# Power_Amplifier.net
KiCad netlist of a schematic drawn in Altium Designer
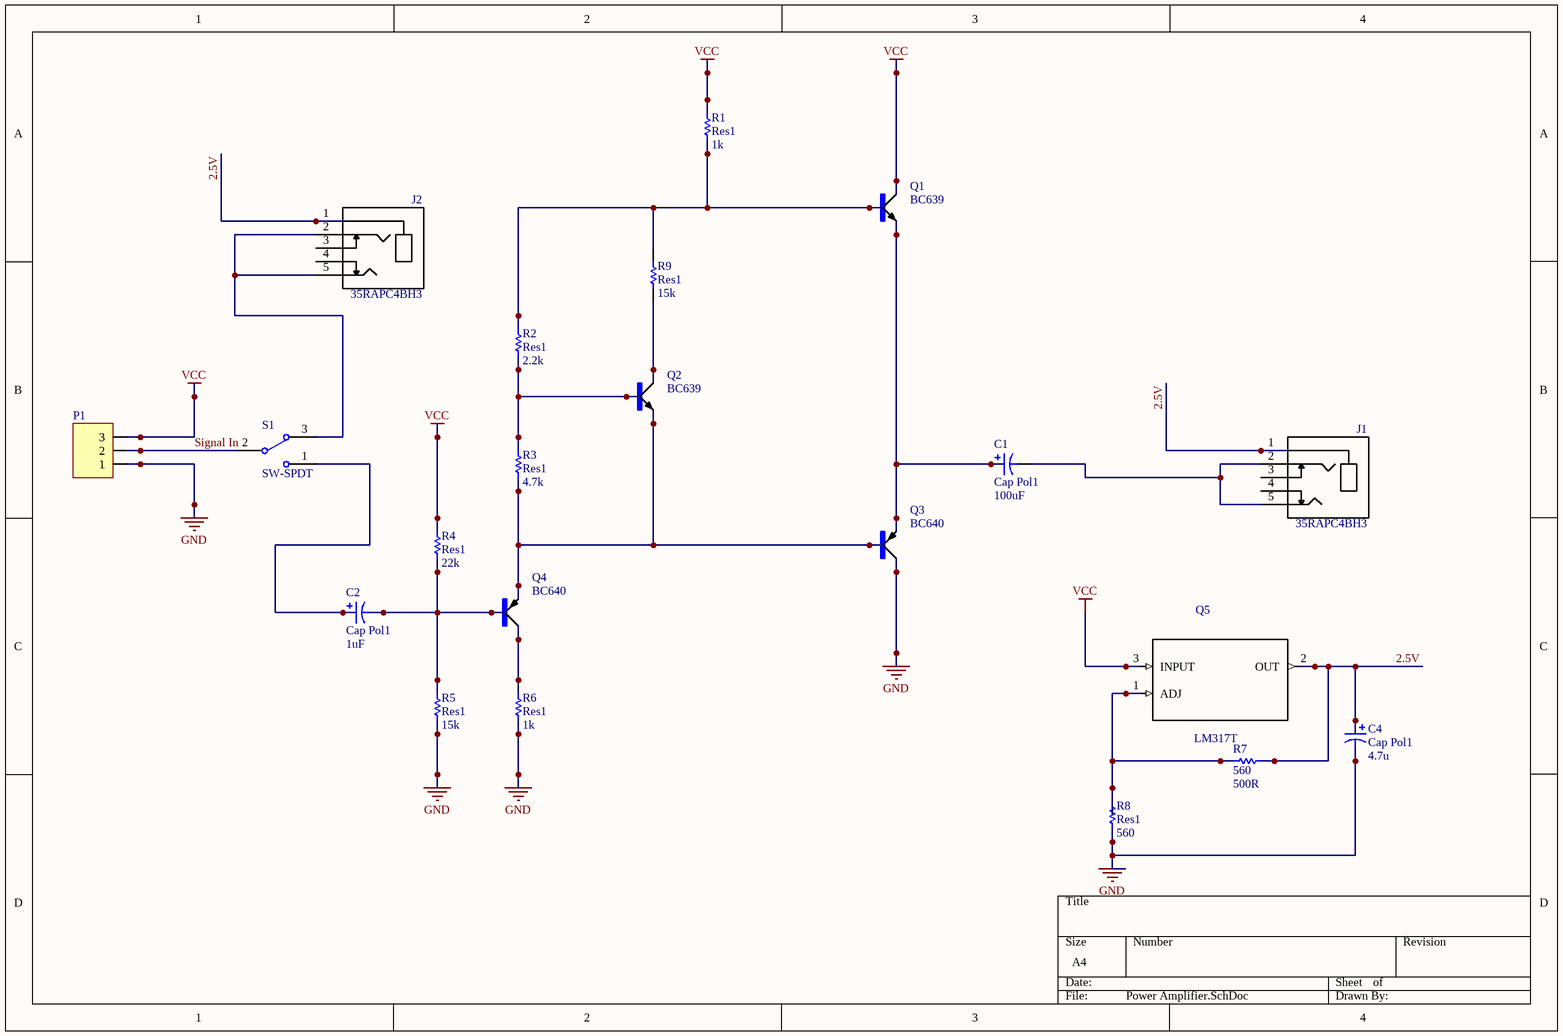
[diagram p0: Power Amplifier.SchDoc]

(export (version "E")
  (design (tool "Eeschema 10.0.6"))
  (components
    (comp (ref "C1")
      (value "Cap Pol1")
      (footprint "Capacitor 5mmx11mm")
      (description "Polarized Capacitor (Radial)")
      (fields (field (name "ALTIUM_VALUE") "100uF") (field (name "PUBLISHER") "Altium Limited"))
      (libsource (lib "Miscellaneous Devices") (part "Cap Pol1"))
    )
    (comp (ref "C2")
      (value "Cap Pol1")
      (footprint "Capacitor 5mmx11mm")
      (description "Polarized Capacitor (Radial)")
      (fields (field (name "ALTIUM_VALUE") "1uF") (field (name "PUBLISHER") "Altium Limited"))
      (libsource (lib "Miscellaneous Devices") (part "Cap Pol1"))
    )
    (comp (ref "C4")
      (value "Cap Pol1")
      (footprint "Capacitor 5mmx11mm")
      (description "Polarized Capacitor (Radial)")
      (fields (field (name "ALTIUM_VALUE") "4.7u") (field (name "PUBLISHER") "Altium Limited"))
      (libsource (lib "Miscellaneous Devices") (part "Cap Pol1"))
    )
    (comp (ref "J1")
      (value "35RAPC4BH3")
      (footprint "*SWITCHCRAFT_35RAPC4BH3")
      (description "3.50mm _0.141, 1/8, Mini Plug_ - Headphone Phone Jack Stereo _3 Conductor, TRS_ Connector Solder")
      (fields (field (name "MF") "Switchcraft Inc."))
      (libsource (lib "35RAPC4BH3") (part "35RAPC4BH3"))
    )
    (comp (ref "J2")
      (value "35RAPC4BH3")
      (footprint "*SWITCHCRAFT_35RAPC4BH3")
      (description "3.50mm _0.141, 1/8, Mini Plug_ - Headphone Phone Jack Stereo _3 Conductor, TRS_ Connector Solder")
      (fields (field (name "MF") "Switchcraft Inc."))
      (libsource (lib "35RAPC4BH3") (part "35RAPC4BH3"))
    )
    (comp (ref "P1")
      (value "~")
      (footprint "HDR1X3")
      (description "Header, 3-Pin")
      (fields (field (name "PUBLISHER") "Altium Limited"))
      (libsource (lib "Miscellaneous Connectors") (part "Header 3"))
    )
    (comp (ref "Q1")
      (value "BC639")
      (footprint "*SOT54D_BC639(Primary)")
      (description "Bipolar _BJT_ Transistor NPN 80V 1A 200MHz 625mW Through Hole TO-92-3")
      (fields (field (name "MF") "ON Semiconductor"))
      (libsource (lib "BC639") (part "BC639"))
    )
    (comp (ref "Q2")
      (value "BC639")
      (footprint "*SOT54D_BC639(Primary)")
      (description "Bipolar _BJT_ Transistor NPN 80V 1A 200MHz 625mW Through Hole TO-92-3")
      (fields (field (name "MF") "ON Semiconductor"))
      (libsource (lib "BC639") (part "BC639"))
    )
    (comp (ref "Q3")
      (value "BC640")
      (footprint "*TO92127P520H534-3")
      (description "Bipolar _BJT_ Transistor PNP 80V 500mA 150MHz 625mW Through Hole TO-92-3")
      (fields (field (name "MF") "ON Semiconductor"))
      (libsource (lib "BC640") (part "BC640"))
    )
    (comp (ref "Q4")
      (value "BC640")
      (footprint "*SOT54D_BC640(Primary)")
      (description "Bipolar _BJT_ Transistor PNP 80V 500mA 150MHz 625mW Through Hole TO-92-3")
      (fields (field (name "MF") "ON Semiconductor"))
      (libsource (lib "BC640") (part "BC640"))
    )
    (comp (ref "Q5")
      (value "LM317T")
      (footprint "TO254P450X1020X2000-3P")
      (fields (field (name "MF") "Texas Instruments") (field (name "DIGI-KEY_PART_NUMBER") "LM317T-ND"))
      (libsource (lib "LM317T") (part "LM317T"))
    )
    (comp (ref "R1")
      (value "Res1")
      (footprint "AXIAL-0.3")
      (description "Resistor")
      (fields (field (name "ALTIUM_VALUE") "1k") (field (name "PUBLISHER") "Altium Limited"))
      (libsource (lib "Miscellaneous Devices") (part "Res1"))
    )
    (comp (ref "R2")
      (value "Res1")
      (footprint "AXIAL-0.3")
      (description "Resistor")
      (fields (field (name "ALTIUM_VALUE") "2.2k") (field (name "PUBLISHER") "Altium Limited"))
      (libsource (lib "Miscellaneous Devices") (part "Res1"))
    )
    (comp (ref "R3")
      (value "Res1")
      (footprint "AXIAL-0.3")
      (description "Resistor")
      (fields (field (name "ALTIUM_VALUE") "4.7k") (field (name "PUBLISHER") "Altium Limited"))
      (libsource (lib "Miscellaneous Devices") (part "Res1"))
    )
    (comp (ref "R4")
      (value "Res1")
      (footprint "AXIAL-0.3")
      (description "Resistor")
      (fields (field (name "ALTIUM_VALUE") "22k") (field (name "PUBLISHER") "Altium Limited"))
      (libsource (lib "Miscellaneous Devices") (part "Res1"))
    )
    (comp (ref "R5")
      (value "Res1")
      (footprint "AXIAL-0.3")
      (description "Resistor")
      (fields (field (name "ALTIUM_VALUE") "15k") (field (name "PUBLISHER") "Altium Limited"))
      (libsource (lib "Miscellaneous Devices") (part "Res1"))
    )
    (comp (ref "R6")
      (value "Res1")
      (footprint "AXIAL-0.3")
      (description "Resistor")
      (fields (field (name "ALTIUM_VALUE") "1k") (field (name "PUBLISHER") "Altium Limited"))
      (libsource (lib "Miscellaneous Devices") (part "Res1"))
    )
    (comp (ref "R7")
      (value "560")
      (footprint "AXIAL-0.3")
      (description "Resistor")
      (fields (field (name "ALTIUM_VALUE") "500R") (field (name "PUBLISHER") "Altium Limited"))
      (libsource (lib "Miscellaneous Devices") (part "Res1"))
    )
    (comp (ref "R8")
      (value "Res1")
      (footprint "AXIAL-0.3")
      (description "Resistor")
      (fields (field (name "ALTIUM_VALUE") "560") (field (name "PUBLISHER") "Altium Limited"))
      (libsource (lib "Miscellaneous Devices") (part "Res1"))
    )
    (comp (ref "R9")
      (value "Res1")
      (footprint "AXIAL-0.3")
      (description "Resistor")
      (fields (field (name "ALTIUM_VALUE") "15k") (field (name "PUBLISHER") "Altium Limited"))
      (libsource (lib "Miscellaneous Devices") (part "Res1"))
    )
    (comp (ref "S1")
      (value "SW-SPDT")
      (footprint "HDR1X3")
      (description "SPDT Subminiature Toggle Switch, Right Angle Mounting, Vertical Actuation")
      (fields (field (name "PUBLISHER") "Altium Limited"))
      (libsource (lib "Miscellaneous Devices") (part "SW-SPDT"))
    )
  )
  (nets
    (net (code "1") (name "/2.5V") (class "Default")
      (node (ref "C4") (pin "1") (pinfunction "1_1") (pintype "passive"))
      (node (ref "J1") (pin "1") (pinfunction "1_1") (pintype "passive"))
      (node (ref "J2") (pin "1") (pinfunction "1_1") (pintype "passive"))
      (node (ref "Q5") (pin "2") (pinfunction "OUT_2") (pintype "output"))
      (node (ref "R7") (pin "2") (pinfunction "2_2") (pintype "passive"))
    )
    (net (code "2") (name "/Signal In") (class "Default")
      (node (ref "P1") (pin "2") (pinfunction "2_2") (pintype "passive"))
      (node (ref "S1") (pin "2") (pinfunction "2_2") (pintype "passive"))
    )
    (net (code "3") (name "GND") (class "Default")
      (node (ref "C4") (pin "2") (pinfunction "2_2") (pintype "passive"))
      (node (ref "P1") (pin "1") (pinfunction "1_1") (pintype "passive"))
      (node (ref "Q3") (pin "C") (pinfunction "C_C") (pintype "passive"))
      (node (ref "R5") (pin "1") (pinfunction "1_1") (pintype "passive"))
      (node (ref "R6") (pin "1") (pinfunction "1_1") (pintype "passive"))
      (node (ref "R8") (pin "1") (pinfunction "1_1") (pintype "passive"))
    )
    (net (code "4") (name "Net-(C1-Pad1)") (class "Default")
      (node (ref "C1") (pin "1") (pinfunction "1_1") (pintype "passive"))
      (node (ref "Q1") (pin "E") (pinfunction "E_E") (pintype "passive"))
      (node (ref "Q3") (pin "E") (pinfunction "E_E") (pintype "passive"))
    )
    (net (code "5") (name "Net-(C1-Pad2)") (class "Default")
      (node (ref "C1") (pin "2") (pinfunction "2_2") (pintype "passive"))
      (node (ref "J1") (pin "2") (pinfunction "2_2") (pintype "passive"))
      (node (ref "J1") (pin "5") (pinfunction "5_5") (pintype "passive"))
    )
    (net (code "6") (name "Net-(C2-Pad1)") (class "Default")
      (node (ref "C2") (pin "1") (pinfunction "1_1") (pintype "passive"))
      (node (ref "S1") (pin "1") (pinfunction "1_1") (pintype "passive"))
    )
    (net (code "7") (name "Net-(C2-Pad2)") (class "Default")
      (node (ref "C2") (pin "2") (pinfunction "2_2") (pintype "passive"))
      (node (ref "Q4") (pin "B") (pinfunction "B_B") (pintype "passive"))
      (node (ref "R4") (pin "1") (pinfunction "1_1") (pintype "passive"))
      (node (ref "R5") (pin "2") (pinfunction "2_2") (pintype "passive"))
    )
    (net (code "8") (name "Net-(J2-Pad2)") (class "Default")
      (node (ref "J2") (pin "2") (pinfunction "2_2") (pintype "passive"))
      (node (ref "J2") (pin "5") (pinfunction "5_5") (pintype "passive"))
      (node (ref "S1") (pin "3") (pinfunction "3_3") (pintype "passive"))
    )
    (net (code "9") (name "Net-(Q1-PadB)") (class "Default")
      (node (ref "Q1") (pin "B") (pinfunction "B_B") (pintype "passive"))
      (node (ref "R1") (pin "1") (pinfunction "1_1") (pintype "passive"))
      (node (ref "R2") (pin "2") (pinfunction "2_2") (pintype "passive"))
      (node (ref "R9") (pin "2") (pinfunction "2_2") (pintype "passive"))
    )
    (net (code "10") (name "Net-(Q2-PadB)") (class "Default")
      (node (ref "Q2") (pin "B") (pinfunction "B_B") (pintype "passive"))
      (node (ref "R2") (pin "1") (pinfunction "1_1") (pintype "passive"))
      (node (ref "R3") (pin "2") (pinfunction "2_2") (pintype "passive"))
    )
    (net (code "11") (name "Net-(Q2-PadC)") (class "Default")
      (node (ref "Q2") (pin "C") (pinfunction "C_C") (pintype "passive"))
      (node (ref "R9") (pin "1") (pinfunction "1_1") (pintype "passive"))
    )
    (net (code "12") (name "Net-(Q2-PadE)") (class "Default")
      (node (ref "Q2") (pin "E") (pinfunction "E_E") (pintype "passive"))
      (node (ref "Q3") (pin "B") (pinfunction "B_B") (pintype "passive"))
      (node (ref "Q4") (pin "E") (pinfunction "E_E") (pintype "passive"))
      (node (ref "R3") (pin "1") (pinfunction "1_1") (pintype "passive"))
    )
    (net (code "13") (name "Net-(Q4-PadC)") (class "Default")
      (node (ref "Q4") (pin "C") (pinfunction "C_C") (pintype "passive"))
      (node (ref "R6") (pin "2") (pinfunction "2_2") (pintype "passive"))
    )
    (net (code "14") (name "Net-(Q5-ADJ)") (class "Default")
      (node (ref "Q5") (pin "1") (pinfunction "ADJ_1") (pintype "input"))
      (node (ref "R7") (pin "1") (pinfunction "1_1") (pintype "passive"))
      (node (ref "R8") (pin "2") (pinfunction "2_2") (pintype "passive"))
    )
    (net (code "15") (name "VCC") (class "Default")
      (node (ref "P1") (pin "3") (pinfunction "3_3") (pintype "passive"))
      (node (ref "Q1") (pin "C") (pinfunction "C_C") (pintype "passive"))
      (node (ref "Q5") (pin "3") (pinfunction "INPUT_3") (pintype "input"))
      (node (ref "R1") (pin "2") (pinfunction "2_2") (pintype "passive"))
      (node (ref "R4") (pin "2") (pinfunction "2_2") (pintype "passive"))
    )
    (net (code "16") (name "unconnected-(J1-Pad3)") (class "Default")
      (node (ref "J1") (pin "3") (pinfunction "3_3") (pintype "passive"))
    )
    (net (code "17") (name "unconnected-(J1-Pad4)") (class "Default")
      (node (ref "J1") (pin "4") (pinfunction "4_4") (pintype "passive"))
    )
    (net (code "18") (name "unconnected-(J2-Pad3)") (class "Default")
      (node (ref "J2") (pin "3") (pinfunction "3_3") (pintype "passive"))
    )
    (net (code "19") (name "unconnected-(J2-Pad4)") (class "Default")
      (node (ref "J2") (pin "4") (pinfunction "4_4") (pintype "passive"))
    )
  )
)
